# Leak_Sensor_Schematic.net
KiCad netlist of a schematic drawn in Altium Designer
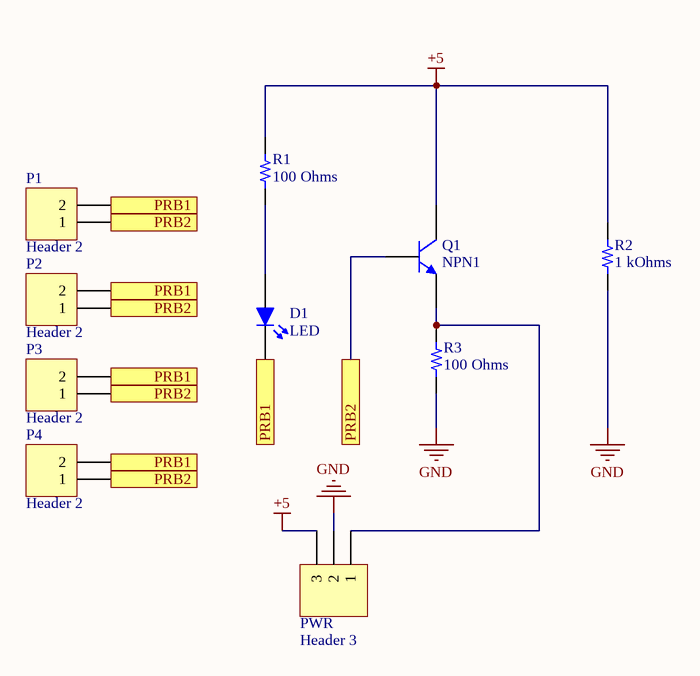
[diagram p0: Leak Sensor Schematic.SchDoc]

(export (version "E")
  (design (tool "Eeschema 10.0.6"))
  (components
    (comp (ref "D1")
      (value "LED")
      (footprint "5mm THT LED")
      (libsource (lib "Main Schematic Library") (part "5mm THT LED"))
    )
    (comp (ref "P1")
      (value "Header 2")
      (footprint "HDR1X2")
      (description "Header, 2-Pin")
      (fields (field (name "PUBLISHER") "Altium Limited"))
      (libsource (lib "Miscellaneous Connectors") (part "Header 2"))
    )
    (comp (ref "P2")
      (value "Header 2")
      (footprint "HDR1X2")
      (description "Header, 2-Pin")
      (fields (field (name "PUBLISHER") "Altium Limited"))
      (libsource (lib "Miscellaneous Connectors") (part "Header 2"))
    )
    (comp (ref "P3")
      (value "Header 2")
      (footprint "HDR1X2")
      (description "Header, 2-Pin")
      (fields (field (name "PUBLISHER") "Altium Limited"))
      (libsource (lib "Miscellaneous Connectors") (part "Header 2"))
    )
    (comp (ref "P4")
      (value "Header 2")
      (footprint "HDR1X2")
      (description "Header, 2-Pin")
      (fields (field (name "PUBLISHER") "Altium Limited"))
      (libsource (lib "Miscellaneous Connectors") (part "Header 2"))
    )
    (comp (ref "PWR")
      (value "Header 3")
      (footprint "HDR1X3")
      (description "Header, 3-Pin")
      (fields (field (name "PUBLISHER") "Altium Limited"))
      (libsource (lib "Miscellaneous Connectors") (part "Header 3"))
    )
    (comp (ref "Q1")
      (value "NPN1")
      (footprint "TO-92")
      (description "NPN Bipolar Transistor")
      (fields (field (name "PUBLISHER") "Altium Limited"))
      (libsource (lib "Miscellaneous Devices") (part "NPN1"))
    )
    (comp (ref "R1")
      (value "100 Ohms")
      (footprint "RES 1210_3225")
      (description "RES 100 OHM 5% 1/2W 1210")
      (fields
        (field (name "PART NUMBER") "RMCF1210JT100R")
        (field (name "MANUFACTURER") "Stackpole Electronics Inc")
      )
      (libsource (lib "Celestial Altium Library - altium_library") (part "Resistor"))
    )
    (comp (ref "R2")
      (value "1 kOhms")
      (footprint "RES 1210_3225")
      (description "RES 1K OHM 5% 1/3W 1210")
      (fields
        (field (name "PART NUMBER") "RMCF1210JT1K00")
        (field (name "MANUFACTURER") "Stackpole Electronics Inc")
      )
      (libsource (lib "Celestial Altium Library - altium_library") (part "Resistor"))
    )
    (comp (ref "R3")
      (value "100 Ohms")
      (footprint "RES 1210_3225")
      (description "RES 100 OHM 5% 1/2W 1210")
      (fields
        (field (name "PART NUMBER") "RMCF1210JT100R")
        (field (name "MANUFACTURER") "Stackpole Electronics Inc")
      )
      (libsource (lib "Celestial Altium Library - altium_library") (part "Resistor"))
    )
  )
  (nets
    (net (code "1") (name "+5") (class "Default")
      (node (ref "PWR") (pin "3") (pinfunction "3_3") (pintype "passive"))
      (node (ref "Q1") (pin "1") (pinfunction "C_1") (pintype "passive"))
      (node (ref "R1") (pin "2") (pinfunction "2_2") (pintype "passive"))
      (node (ref "R2") (pin "2") (pinfunction "2_2") (pintype "passive"))
    )
    (net (code "2") (name "/PRB1") (class "Default")
      (node (ref "D1") (pin "2") (pintype "passive"))
      (node (ref "P1") (pin "2") (pinfunction "2_2") (pintype "passive"))
      (node (ref "P2") (pin "2") (pinfunction "2_2") (pintype "passive"))
      (node (ref "P3") (pin "2") (pinfunction "2_2") (pintype "passive"))
      (node (ref "P4") (pin "2") (pinfunction "2_2") (pintype "passive"))
    )
    (net (code "3") (name "/PRB2") (class "Default")
      (node (ref "P1") (pin "1") (pinfunction "1_1") (pintype "passive"))
      (node (ref "P2") (pin "1") (pinfunction "1_1") (pintype "passive"))
      (node (ref "P3") (pin "1") (pinfunction "1_1") (pintype "passive"))
      (node (ref "P4") (pin "1") (pinfunction "1_1") (pintype "passive"))
      (node (ref "Q1") (pin "2") (pinfunction "B_2") (pintype "passive"))
    )
    (net (code "4") (name "GND") (class "Default")
      (node (ref "PWR") (pin "2") (pinfunction "2_2") (pintype "passive"))
      (node (ref "R2") (pin "1") (pinfunction "1_1") (pintype "passive"))
      (node (ref "R3") (pin "1") (pinfunction "1_1") (pintype "passive"))
    )
    (net (code "5") (name "Net-(D1-Pad1)") (class "Default")
      (node (ref "D1") (pin "1") (pintype "passive"))
      (node (ref "R1") (pin "1") (pinfunction "1_1") (pintype "passive"))
    )
    (net (code "6") (name "Net-(Q1-E)") (class "Default")
      (node (ref "PWR") (pin "1") (pinfunction "1_1") (pintype "passive"))
      (node (ref "Q1") (pin "3") (pinfunction "E_3") (pintype "passive"))
      (node (ref "R3") (pin "2") (pinfunction "2_2") (pintype "passive"))
    )
  )
)
